# 7d_-_Sensors.net
KiCad netlist of a schematic drawn in Altium Designer
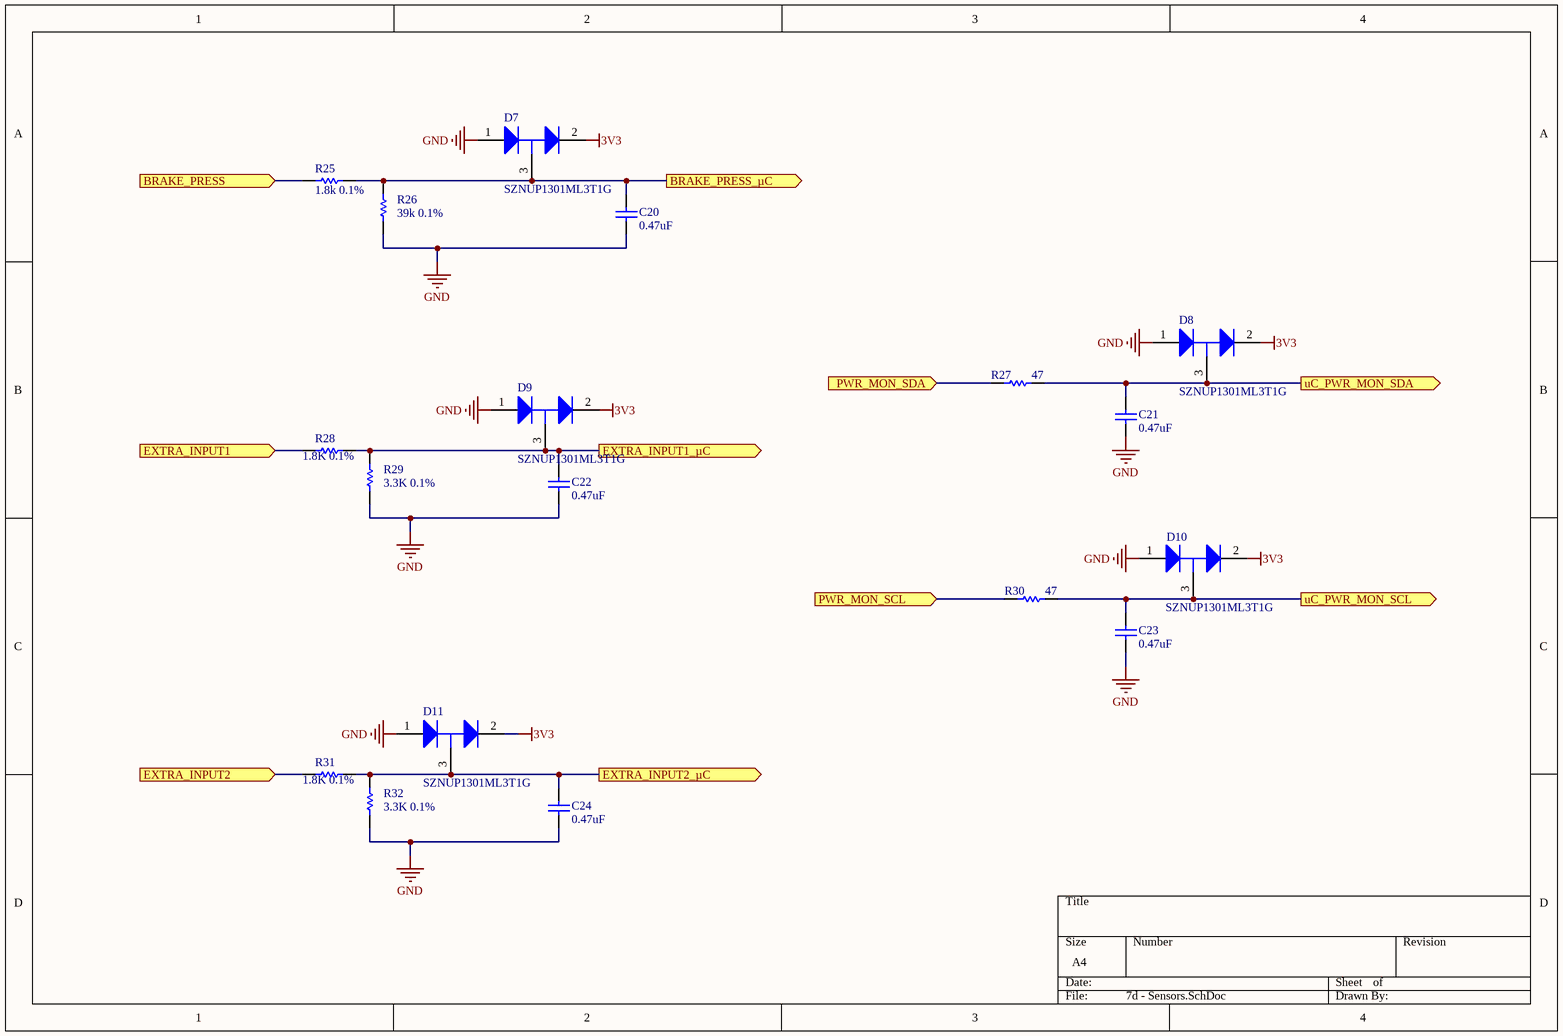
[diagram p0: 7d - Sensors.SchDoc]

(export (version "E")
  (design (tool "Eeschema 10.0.6"))
  (components
    (comp (ref "C20")
      (value "0.47uF")
      (footprint "1608[0603]")
      (description "Capacitor")
      (fields (field (name "Comment") "Cap") (field (name "PUBLISHER") "Altium Limited"))
      (libsource (lib "Miscellaneous Devices") (part "Cap"))
    )
    (comp (ref "C21")
      (value "0.47uF")
      (footprint "1608[0603]")
      (description "Capacitor")
      (fields (field (name "Comment") "Cap") (field (name "PUBLISHER") "Altium Limited"))
      (libsource (lib "Miscellaneous Devices") (part "Cap"))
    )
    (comp (ref "C22")
      (value "0.47uF")
      (footprint "1608[0603]")
      (description "Capacitor")
      (fields (field (name "Comment") "Cap") (field (name "PUBLISHER") "Altium Limited"))
      (libsource (lib "Miscellaneous Devices") (part "Cap"))
    )
    (comp (ref "C23")
      (value "0.47uF")
      (footprint "1608[0603]")
      (description "Capacitor")
      (fields (field (name "Comment") "Cap") (field (name "PUBLISHER") "Altium Limited"))
      (libsource (lib "Miscellaneous Devices") (part "Cap"))
    )
    (comp (ref "C24")
      (value "0.47uF")
      (footprint "1608[0603]")
      (description "Capacitor")
      (fields (field (name "Comment") "Cap") (field (name "PUBLISHER") "Altium Limited"))
      (libsource (lib "Miscellaneous Devices") (part "Cap"))
    )
    (comp (ref "D7")
      (value "SZNUP1301ML3T1G")
      (footprint "ONSC-SOT-23-3-318-08_V")
      (fields (field (name "MANUFACTURER") "On Semiconductor"))
      (libsource (lib "Altium Content Vault") (part "ONSC-NUP1301-SOT-23-3-318-08"))
    )
    (comp (ref "D8")
      (value "SZNUP1301ML3T1G")
      (footprint "ONSC-SOT-23-3-318-08_V")
      (fields (field (name "MANUFACTURER") "On Semiconductor"))
      (libsource (lib "Altium Content Vault") (part "ONSC-NUP1301-SOT-23-3-318-08"))
    )
    (comp (ref "D9")
      (value "SZNUP1301ML3T1G")
      (footprint "ONSC-SOT-23-3-318-08_V")
      (fields (field (name "MANUFACTURER") "On Semiconductor"))
      (libsource (lib "Altium Content Vault") (part "ONSC-NUP1301-SOT-23-3-318-08"))
    )
    (comp (ref "D10")
      (value "SZNUP1301ML3T1G")
      (footprint "ONSC-SOT-23-3-318-08_V")
      (fields (field (name "MANUFACTURER") "On Semiconductor"))
      (libsource (lib "Altium Content Vault") (part "ONSC-NUP1301-SOT-23-3-318-08"))
    )
    (comp (ref "D11")
      (value "SZNUP1301ML3T1G")
      (footprint "ONSC-SOT-23-3-318-08_V")
      (fields (field (name "MANUFACTURER") "On Semiconductor"))
      (libsource (lib "Altium Content Vault") (part "ONSC-NUP1301-SOT-23-3-318-08"))
    )
    (comp (ref "R25")
      (value "1.8k 0.1%")
      (footprint "1608[0603]")
      (description "Resistor")
      (fields (field (name "Comment") "Res1") (field (name "PUBLISHER") "Altium Limited"))
      (libsource (lib "Miscellaneous Devices") (part "Res1"))
    )
    (comp (ref "R26")
      (value "39k 0.1%")
      (footprint "1608[0603]")
      (description "Resistor")
      (fields (field (name "Comment") "Res1") (field (name "PUBLISHER") "Altium Limited"))
      (libsource (lib "Miscellaneous Devices") (part "Res1"))
    )
    (comp (ref "R27")
      (value "47")
      (footprint "1608[0603]")
      (description "Resistor")
      (fields (field (name "Comment") "Res1") (field (name "PUBLISHER") "Altium Limited"))
      (libsource (lib "Miscellaneous Devices") (part "Res1"))
    )
    (comp (ref "R28")
      (value "1.8K 0.1%")
      (footprint "1608[0603]")
      (description "Resistor")
      (fields (field (name "Comment") "Res1") (field (name "PUBLISHER") "Altium Limited"))
      (libsource (lib "Miscellaneous Devices") (part "Res1"))
    )
    (comp (ref "R29")
      (value "3.3K 0.1%")
      (footprint "1608[0603]")
      (description "Resistor")
      (fields (field (name "Comment") "Res1") (field (name "PUBLISHER") "Altium Limited"))
      (libsource (lib "Miscellaneous Devices") (part "Res1"))
    )
    (comp (ref "R30")
      (value "47")
      (footprint "1608[0603]")
      (description "Resistor")
      (fields (field (name "Comment") "Res1") (field (name "PUBLISHER") "Altium Limited"))
      (libsource (lib "Miscellaneous Devices") (part "Res1"))
    )
    (comp (ref "R31")
      (value "1.8K 0.1%")
      (footprint "1608[0603]")
      (description "Resistor")
      (fields (field (name "Comment") "Res1") (field (name "PUBLISHER") "Altium Limited"))
      (libsource (lib "Miscellaneous Devices") (part "Res1"))
    )
    (comp (ref "R32")
      (value "3.3K 0.1%")
      (footprint "1608[0603]")
      (description "Resistor")
      (fields (field (name "Comment") "Res1") (field (name "PUBLISHER") "Altium Limited"))
      (libsource (lib "Miscellaneous Devices") (part "Res1"))
    )
  )
  (nets
    (net (code "1") (name "/BRAKE_PRESS") (class "Default")
      (node (ref "R25") (pin "2") (pinfunction "2_2") (pintype "passive"))
    )
    (net (code "2") (name "/BRAKE_PRESS_µC") (class "Default")
      (node (ref "C20") (pin "2") (pinfunction "2_2") (pintype "passive"))
      (node (ref "D7") (pin "3") (pinfunction "K/A_3") (pintype "passive"))
      (node (ref "R25") (pin "1") (pinfunction "1_1") (pintype "passive"))
      (node (ref "R26") (pin "2") (pinfunction "2_2") (pintype "passive"))
    )
    (net (code "3") (name "/EXTRA_INPUT1") (class "Default")
      (node (ref "R28") (pin "2") (pinfunction "2_2") (pintype "passive"))
    )
    (net (code "4") (name "/EXTRA_INPUT1_µC") (class "Default")
      (node (ref "C22") (pin "2") (pinfunction "2_2") (pintype "passive"))
      (node (ref "D9") (pin "3") (pinfunction "K/A_3") (pintype "passive"))
      (node (ref "R28") (pin "1") (pinfunction "1_1") (pintype "passive"))
      (node (ref "R29") (pin "2") (pinfunction "2_2") (pintype "passive"))
    )
    (net (code "5") (name "/EXTRA_INPUT2") (class "Default")
      (node (ref "R31") (pin "2") (pinfunction "2_2") (pintype "passive"))
    )
    (net (code "6") (name "/EXTRA_INPUT2_µC") (class "Default")
      (node (ref "C24") (pin "2") (pinfunction "2_2") (pintype "passive"))
      (node (ref "D11") (pin "3") (pinfunction "K/A_3") (pintype "passive"))
      (node (ref "R31") (pin "1") (pinfunction "1_1") (pintype "passive"))
      (node (ref "R32") (pin "2") (pinfunction "2_2") (pintype "passive"))
    )
    (net (code "7") (name "/PWR_MON_SCL") (class "Default")
      (node (ref "R30") (pin "1") (pinfunction "1_1") (pintype "passive"))
    )
    (net (code "8") (name "/PWR_MON_SDA") (class "Default")
      (node (ref "R27") (pin "1") (pinfunction "1_1") (pintype "passive"))
    )
    (net (code "9") (name "/uC_PWR_MON_SCL") (class "Default")
      (node (ref "C23") (pin "2") (pinfunction "2_2") (pintype "passive"))
      (node (ref "D10") (pin "3") (pinfunction "K/A_3") (pintype "passive"))
      (node (ref "R30") (pin "2") (pinfunction "2_2") (pintype "passive"))
    )
    (net (code "10") (name "/uC_PWR_MON_SDA") (class "Default")
      (node (ref "C21") (pin "2") (pinfunction "2_2") (pintype "passive"))
      (node (ref "D8") (pin "3") (pinfunction "K/A_3") (pintype "passive"))
      (node (ref "R27") (pin "2") (pinfunction "2_2") (pintype "passive"))
    )
    (net (code "11") (name "3V3") (class "Default")
      (node (ref "D10") (pin "2") (pinfunction "K_2") (pintype "passive"))
      (node (ref "D11") (pin "2") (pinfunction "K_2") (pintype "passive"))
      (node (ref "D7") (pin "2") (pinfunction "K_2") (pintype "passive"))
      (node (ref "D8") (pin "2") (pinfunction "K_2") (pintype "passive"))
      (node (ref "D9") (pin "2") (pinfunction "K_2") (pintype "passive"))
    )
    (net (code "12") (name "GND") (class "Default")
      (node (ref "C20") (pin "1") (pinfunction "1_1") (pintype "passive"))
      (node (ref "C21") (pin "1") (pinfunction "1_1") (pintype "passive"))
      (node (ref "C22") (pin "1") (pinfunction "1_1") (pintype "passive"))
      (node (ref "C23") (pin "1") (pinfunction "1_1") (pintype "passive"))
      (node (ref "C24") (pin "1") (pinfunction "1_1") (pintype "passive"))
      (node (ref "D10") (pin "1") (pinfunction "A_1") (pintype "passive"))
      (node (ref "D11") (pin "1") (pinfunction "A_1") (pintype "passive"))
      (node (ref "D7") (pin "1") (pinfunction "A_1") (pintype "passive"))
      (node (ref "D8") (pin "1") (pinfunction "A_1") (pintype "passive"))
      (node (ref "D9") (pin "1") (pinfunction "A_1") (pintype "passive"))
      (node (ref "R26") (pin "1") (pinfunction "1_1") (pintype "passive"))
      (node (ref "R29") (pin "1") (pinfunction "1_1") (pintype "passive"))
      (node (ref "R32") (pin "1") (pinfunction "1_1") (pintype "passive"))
    )
  )
)
